# Sprite_Sail.net
KiCad netlist of a schematic drawn in EAGLE
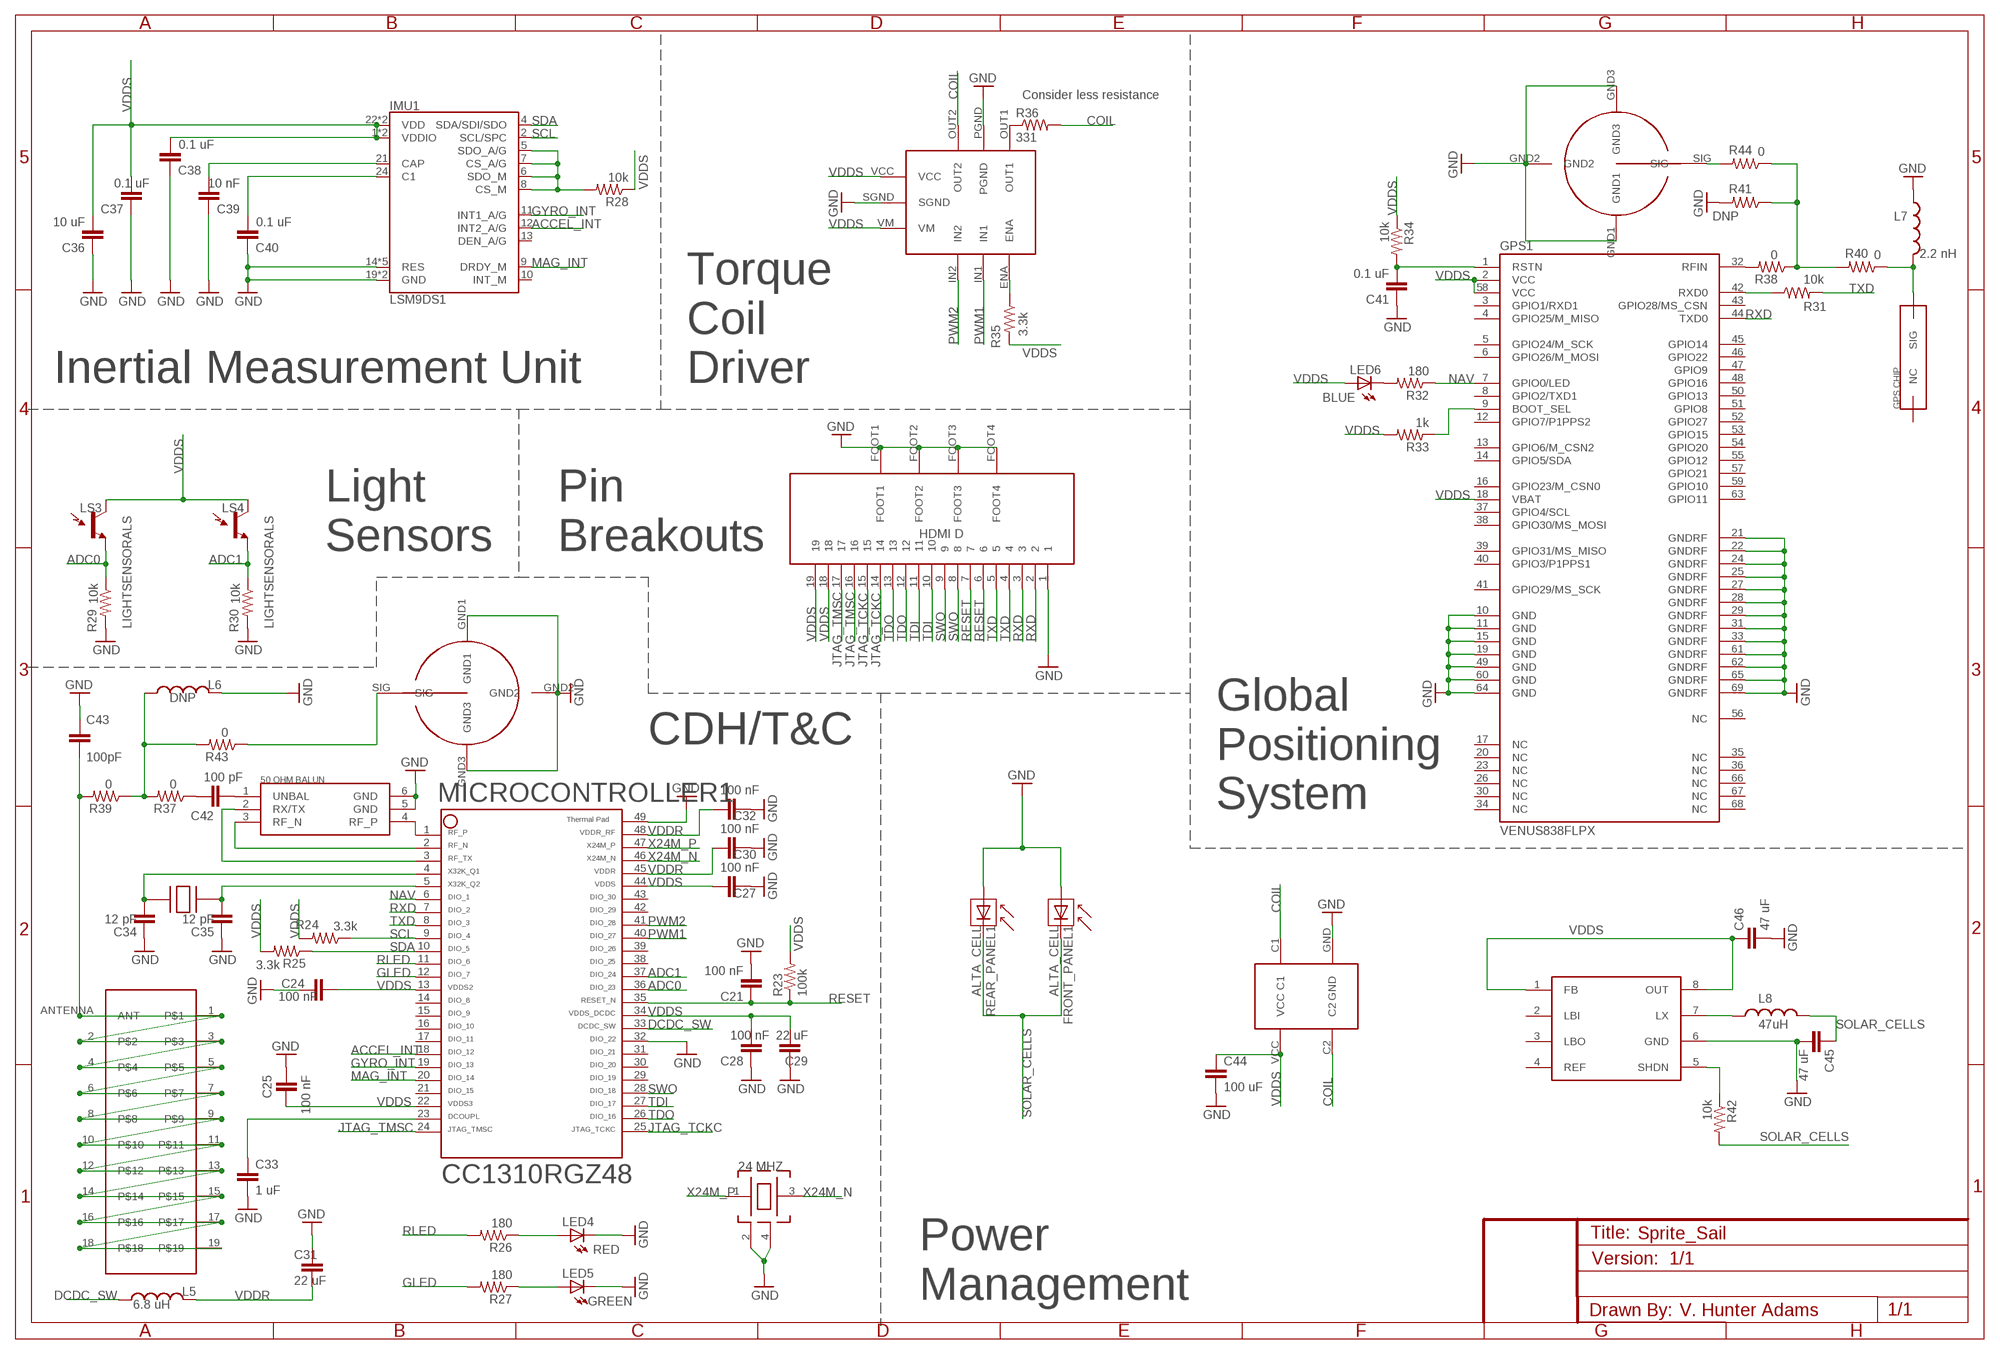
[diagram p0: schematic, sheet 1]

(export (version "E")
  (design (tool "Eeschema 10.0.6"))
  (components
    (comp (ref "32.1")
      (value "FC-135")
      (footprint "eagle-import:FC-135")
      (libsource (lib "eagle-import") (part "FC-135"))
    )
    (comp (ref "BALUN1")
      (value "JOHANSON_BALUN")
      (footprint "eagle-import:JOHANSON_BALUN")
      (libsource (lib "eagle-import") (part "JOHANSON_BALUN"))
    )
    (comp (ref "C21")
      (value "100 nF")
      (footprint "eagle-import:0402-CAP")
      (libsource (lib "eagle-import") (part "CAP0402-CAP"))
    )
    (comp (ref "C24")
      (value "100 nF")
      (footprint "eagle-import:0402-CAP")
      (libsource (lib "eagle-import") (part "CAP0402-CAP"))
    )
    (comp (ref "C25")
      (value "100 nF")
      (footprint "eagle-import:0402-CAP")
      (libsource (lib "eagle-import") (part "CAP0402-CAP"))
    )
    (comp (ref "C27")
      (value "100 nF")
      (footprint "eagle-import:0402-CAP")
      (libsource (lib "eagle-import") (part "CAP0402-CAP"))
    )
    (comp (ref "C28")
      (value "100 nF")
      (footprint "eagle-import:0402-CAP")
      (libsource (lib "eagle-import") (part "CAP0402-CAP"))
    )
    (comp (ref "C29")
      (value "22 uF")
      (footprint "eagle-import:0402-CAP")
      (libsource (lib "eagle-import") (part "CAP0402-CAP"))
    )
    (comp (ref "C30")
      (value "100 nF")
      (footprint "eagle-import:0402-CAP")
      (libsource (lib "eagle-import") (part "CAP0402-CAP"))
    )
    (comp (ref "C31")
      (value "22 uF")
      (footprint "eagle-import:0402-CAP")
      (libsource (lib "eagle-import") (part "CAP0402-CAP"))
    )
    (comp (ref "C32")
      (value "100 nF")
      (footprint "eagle-import:0402-CAP")
      (libsource (lib "eagle-import") (part "CAP0402-CAP"))
    )
    (comp (ref "C33")
      (value "1 uF")
      (footprint "eagle-import:0402-CAP")
      (libsource (lib "eagle-import") (part "CAP0402-CAP"))
    )
    (comp (ref "C34")
      (value "12 pF")
      (footprint "eagle-import:0402-CAP")
      (libsource (lib "eagle-import") (part "CAP0402-CAP"))
    )
    (comp (ref "C35")
      (value "12 pF")
      (footprint "eagle-import:0402-CAP")
      (libsource (lib "eagle-import") (part "CAP0402-CAP"))
    )
    (comp (ref "C36")
      (value "10 uF")
      (footprint "eagle-import:0402-CAP")
      (libsource (lib "eagle-import") (part "CAP0402-CAP"))
    )
    (comp (ref "C37")
      (value "0.1 uF")
      (footprint "eagle-import:0402-CAP")
      (libsource (lib "eagle-import") (part "CAP0402-CAP"))
    )
    (comp (ref "C38")
      (value "0.1 uF")
      (footprint "eagle-import:0402-CAP")
      (libsource (lib "eagle-import") (part "CAP0402-CAP"))
    )
    (comp (ref "C39")
      (value "10 nF")
      (footprint "eagle-import:0402-CAP")
      (libsource (lib "eagle-import") (part "CAP0402-CAP"))
    )
    (comp (ref "C40")
      (value "0.1 uF")
      (footprint "eagle-import:0402-CAP")
      (libsource (lib "eagle-import") (part "CAP0402-CAP"))
    )
    (comp (ref "C41")
      (value "0.1 uF")
      (footprint "eagle-import:0402-CAP")
      (libsource (lib "eagle-import") (part "CAP0402-CAP"))
    )
    (comp (ref "C42")
      (value "100 pF")
      (footprint "eagle-import:0402-CAP")
      (libsource (lib "eagle-import") (part "CAP0402-CAP"))
    )
    (comp (ref "C43")
      (value "100pF")
      (footprint "eagle-import:0603-CAP")
      (libsource (lib "eagle-import") (part "CAP0603-CAP"))
    )
    (comp (ref "C44")
      (value "100 uF")
      (footprint "eagle-import:0805")
      (libsource (lib "eagle-import") (part "CAP0805"))
    )
    (comp (ref "C45")
      (value "47 uF")
      (footprint "eagle-import:0805")
      (libsource (lib "eagle-import") (part "CAP0805"))
    )
    (comp (ref "C46")
      (value "47 uF")
      (footprint "eagle-import:0805")
      (libsource (lib "eagle-import") (part "CAP0805"))
    )
    (comp (ref "FRONT_PANEL1")
      (value "ALTA_CELL")
      (footprint "eagle-import:ALTA_CELL")
      (libsource (lib "eagle-import") (part "ALTA_CELL"))
    )
    (comp (ref "GPS1")
      (value "VENUS838FLPX")
      (footprint "eagle-import:VENUS838FLPX")
      (libsource (lib "eagle-import") (part "VENUS838FLPX"))
    )
    (comp (ref "IMU1")
      (value "LSM9DS1")
      (footprint "eagle-import:LGA24-8X4")
      (libsource (lib "eagle-import") (part "LSM9DS1"))
    )
    (comp (ref "L5")
      (value "6.8 uH")
      (footprint "eagle-import:0603")
      (libsource (lib "eagle-import") (part "INDUCTOR0603"))
    )
    (comp (ref "L6")
      (value "DNP")
      (footprint "eagle-import:0603")
      (libsource (lib "eagle-import") (part "INDUCTOR0603"))
    )
    (comp (ref "L7")
      (value "2.2 nH")
      (footprint "eagle-import:0603")
      (libsource (lib "eagle-import") (part "INDUCTOR0603"))
    )
    (comp (ref "L8")
      (value "47uH")
      (footprint "eagle-import:0603")
      (libsource (lib "eagle-import") (part "INDUCTOR0603"))
    )
    (comp (ref "LED4")
      (value "RED")
      (footprint "eagle-import:LED-0603")
      (libsource (lib "eagle-import") (part "LED0603"))
    )
    (comp (ref "LED5")
      (value "GREEN")
      (footprint "eagle-import:LED-0603")
      (libsource (lib "eagle-import") (part "LED0603"))
    )
    (comp (ref "LED6")
      (value "BLUE")
      (footprint "eagle-import:LED-0603")
      (libsource (lib "eagle-import") (part "LED0603"))
    )
    (comp (ref "LS3")
      (value "LIGHTSENSORALS")
      (footprint "eagle-import:ALS-PT19")
      (libsource (lib "eagle-import") (part "LIGHTSENSORALS"))
    )
    (comp (ref "LS4")
      (value "LIGHTSENSORALS")
      (footprint "eagle-import:ALS-PT19")
      (libsource (lib "eagle-import") (part "LIGHTSENSORALS"))
    )
    (comp (ref "MICROCONTROLLER1")
      (value "CC1310")
      (footprint "eagle-import:CC1310")
      (libsource (lib "eagle-import") (part "CC1310"))
    )
    (comp (ref "R23")
      (value "100k")
      (footprint "eagle-import:0402-RES")
      (libsource (lib "eagle-import") (part "RESISTOR0402-RES"))
    )
    (comp (ref "R24")
      (value "3.3k")
      (footprint "eagle-import:0402-RES")
      (libsource (lib "eagle-import") (part "RESISTOR0402-RES"))
    )
    (comp (ref "R25")
      (value "3.3k")
      (footprint "eagle-import:0402-RES")
      (libsource (lib "eagle-import") (part "RESISTOR0402-RES"))
    )
    (comp (ref "R26")
      (value "180")
      (footprint "eagle-import:0402-RES")
      (libsource (lib "eagle-import") (part "RESISTOR0402-RES"))
    )
    (comp (ref "R27")
      (value "180")
      (footprint "eagle-import:0402-RES")
      (libsource (lib "eagle-import") (part "RESISTOR0402-RES"))
    )
    (comp (ref "R28")
      (value "10k")
      (footprint "eagle-import:0402-RES")
      (libsource (lib "eagle-import") (part "RESISTOR0402-RES"))
    )
    (comp (ref "R29")
      (value "10k")
      (footprint "eagle-import:0402-RES")
      (libsource (lib "eagle-import") (part "RESISTOR0402-RES"))
    )
    (comp (ref "R30")
      (value "10k")
      (footprint "eagle-import:0402-RES")
      (libsource (lib "eagle-import") (part "RESISTOR0402-RES"))
    )
    (comp (ref "R31")
      (value "10k")
      (footprint "eagle-import:0402-RES")
      (libsource (lib "eagle-import") (part "RESISTOR0402-RES"))
    )
    (comp (ref "R32")
      (value "180")
      (footprint "eagle-import:0402-RES")
      (libsource (lib "eagle-import") (part "RESISTOR0402-RES"))
    )
    (comp (ref "R33")
      (value "1k")
      (footprint "eagle-import:0402-RES")
      (libsource (lib "eagle-import") (part "RESISTOR0402-RES"))
    )
    (comp (ref "R34")
      (value "10k")
      (footprint "eagle-import:0402-RES")
      (libsource (lib "eagle-import") (part "RESISTOR0402-RES"))
    )
    (comp (ref "R35")
      (value "3.3k")
      (footprint "eagle-import:0402-RES")
      (libsource (lib "eagle-import") (part "RESISTOR0402-RES"))
    )
    (comp (ref "R36")
      (value "331")
      (footprint "eagle-import:0402-RES")
      (libsource (lib "eagle-import") (part "RESISTOR0402-RES"))
    )
    (comp (ref "R37")
      (value "0")
      (footprint "eagle-import:0603-RES")
      (libsource (lib "eagle-import") (part "RESISTOR0603-RES"))
    )
    (comp (ref "R38")
      (value "0")
      (footprint "eagle-import:0603-RES")
      (libsource (lib "eagle-import") (part "RESISTOR0603-RES"))
    )
    (comp (ref "R39")
      (value "0")
      (footprint "eagle-import:0603-RES")
      (libsource (lib "eagle-import") (part "RESISTOR0603-RES"))
    )
    (comp (ref "R40")
      (value "0")
      (footprint "eagle-import:0603-RES")
      (libsource (lib "eagle-import") (part "RESISTOR0603-RES"))
    )
    (comp (ref "R41")
      (value "DNP")
      (footprint "eagle-import:0603-RES")
      (libsource (lib "eagle-import") (part "RESISTOR0603-RES"))
    )
    (comp (ref "R42")
      (value "10k")
      (footprint "eagle-import:0402-RES")
      (libsource (lib "eagle-import") (part "RESISTOR0402-RES"))
    )
    (comp (ref "R43")
      (value "0")
      (footprint "eagle-import:0603-RES")
      (libsource (lib "eagle-import") (part "RESISTOR0603-RES"))
    )
    (comp (ref "R44")
      (value "0")
      (footprint "eagle-import:0603-RES")
      (libsource (lib "eagle-import") (part "RESISTOR0603-RES"))
    )
    (comp (ref "REAR_PANEL1")
      (value "ALTA_CELL")
      (footprint "eagle-import:ALTA_CELL")
      (libsource (lib "eagle-import") (part "ALTA_CELL"))
    )
    (comp (ref "TSX1")
      (value "TSX-3225")
      (footprint "eagle-import:TSX-3225")
      (libsource (lib "eagle-import") (part "TSX-3225"))
    )
    (comp (ref "U$1")
      (value "LV8417CS")
      (footprint "eagle-import:LV8417CS")
      (libsource (lib "eagle-import") (part "LV8417CS"))
    )
    (comp (ref "U$10")
      (value "JOHANSON_GPS_CHIP")
      (footprint "eagle-import:JOHANSON_GPS_CHIP")
      (libsource (lib "eagle-import") (part "JOHANSON_GPS_CHIP"))
    )
    (comp (ref "U$11")
      (value "PANASONIC_RECTIFIER")
      (footprint "eagle-import:PANASONIC_RECTIFIER")
      (libsource (lib "eagle-import") (part "PANASONIC_RECTIFIER"))
    )
    (comp (ref "U$12")
      (value "PCB_ANTENNA")
      (footprint "eagle-import:PCB_ANTENNA")
      (libsource (lib "eagle-import") (part "PCB_ANTENNA"))
    )
    (comp (ref "U$13")
      (value "MM5329-2700")
      (footprint "eagle-import:MM5829-2700")
      (libsource (lib "eagle-import") (part "MM5329-2700"))
    )
    (comp (ref "U$14")
      (value "MM5329-2700")
      (footprint "eagle-import:MM5829-2700")
      (libsource (lib "eagle-import") (part "MM5329-2700"))
    )
    (comp (ref "U$15")
      (value "L6920")
      (footprint "eagle-import:L6920")
      (libsource (lib "eagle-import") (part "L6920"))
    )
    (comp (ref "U$16")
      (value "HDMID")
      (footprint "eagle-import:HDMID")
      (libsource (lib "eagle-import") (part "HDMID"))
    )
  )
  (nets
    (net (code "1") (name "/ACCEL_INT") (class "Default")
      (node (ref "IMU1") (pin "12") (pinfunction "INT2_A/G_12") (pintype "bidirectional"))
      (node (ref "MICROCONTROLLER1") (pin "18") (pinfunction "18_18") (pintype "bidirectional"))
    )
    (net (code "2") (name "/ADC0") (class "Default")
      (node (ref "LS3") (pin "E") (pinfunction "E1_E") (pintype "passive"))
      (node (ref "MICROCONTROLLER1") (pin "36") (pinfunction "36_36") (pintype "bidirectional"))
      (node (ref "R29") (pin "1") (pinfunction "1_1") (pintype "passive"))
    )
    (net (code "3") (name "/ADC1") (class "Default")
      (node (ref "LS4") (pin "E") (pinfunction "E1_E") (pintype "passive"))
      (node (ref "MICROCONTROLLER1") (pin "37") (pinfunction "37_37") (pintype "bidirectional"))
      (node (ref "R30") (pin "1") (pinfunction "1_1") (pintype "passive"))
    )
    (net (code "4") (name "/COIL") (class "Default")
      (node (ref "R36") (pin "2") (pinfunction "2_2") (pintype "passive"))
      (node (ref "U$1") (pin "OUT2") (pinfunction "OUT2_OUT2") (pintype "bidirectional"))
      (node (ref "U$11") (pin "C1") (pinfunction "C1_C1") (pintype "bidirectional"))
      (node (ref "U$11") (pin "C2") (pinfunction "C2_C2") (pintype "bidirectional"))
    )
    (net (code "5") (name "/DCDC_SW") (class "Default")
      (node (ref "L5") (pin "1") (pinfunction "1_1") (pintype "passive"))
      (node (ref "MICROCONTROLLER1") (pin "33") (pinfunction "33_33") (pintype "power_in"))
    )
    (net (code "6") (name "/GLED") (class "Default")
      (node (ref "MICROCONTROLLER1") (pin "12") (pinfunction "12_12") (pintype "bidirectional"))
      (node (ref "R27") (pin "2") (pinfunction "2_2") (pintype "passive"))
    )
    (net (code "7") (name "/GYRO_INT") (class "Default")
      (node (ref "IMU1") (pin "11") (pinfunction "INT1_A/G_11") (pintype "bidirectional"))
      (node (ref "MICROCONTROLLER1") (pin "19") (pinfunction "19_19") (pintype "bidirectional"))
    )
    (net (code "8") (name "/JTAG_TCKC") (class "Default")
      (node (ref "MICROCONTROLLER1") (pin "25") (pinfunction "25_25") (pintype "input"))
      (node (ref "U$16") (pin "14") (pinfunction "14_14") (pintype "bidirectional"))
      (node (ref "U$16") (pin "15") (pinfunction "15_15") (pintype "bidirectional"))
    )
    (net (code "9") (name "/JTAG_TMSC") (class "Default")
      (node (ref "MICROCONTROLLER1") (pin "24") (pinfunction "24_24") (pintype "bidirectional"))
      (node (ref "U$16") (pin "16") (pinfunction "16_16") (pintype "bidirectional"))
      (node (ref "U$16") (pin "17") (pinfunction "17_17") (pintype "bidirectional"))
    )
    (net (code "10") (name "/MAG_INT") (class "Default")
      (node (ref "IMU1") (pin "9") (pinfunction "DRDY_M_9") (pintype "bidirectional"))
      (node (ref "MICROCONTROLLER1") (pin "20") (pinfunction "20_20") (pintype "bidirectional"))
    )
    (net (code "11") (name "/NAV") (class "Default")
      (node (ref "GPS1") (pin "7") (pinfunction "GPIO0/LED_7") (pintype "bidirectional"))
      (node (ref "MICROCONTROLLER1") (pin "6") (pinfunction "6_6") (pintype "bidirectional"))
      (node (ref "R32") (pin "1") (pinfunction "1_1") (pintype "passive"))
    )
    (net (code "12") (name "/PWM1") (class "Default")
      (node (ref "MICROCONTROLLER1") (pin "40") (pinfunction "40_40") (pintype "bidirectional"))
      (node (ref "U$1") (pin "IN1") (pinfunction "IN1_IN1") (pintype "bidirectional"))
    )
    (net (code "13") (name "/PWM2") (class "Default")
      (node (ref "MICROCONTROLLER1") (pin "41") (pinfunction "41_41") (pintype "bidirectional"))
      (node (ref "U$1") (pin "IN2") (pinfunction "IN2_IN2") (pintype "bidirectional"))
    )
    (net (code "14") (name "/RESET") (class "Default")
      (node (ref "C21") (pin "1") (pinfunction "1_1") (pintype "passive"))
      (node (ref "MICROCONTROLLER1") (pin "35") (pinfunction "35_35") (pintype "input"))
      (node (ref "R23") (pin "1") (pinfunction "1_1") (pintype "passive"))
      (node (ref "U$16") (pin "6") (pinfunction "6_6") (pintype "bidirectional"))
      (node (ref "U$16") (pin "7") (pinfunction "7_7") (pintype "bidirectional"))
    )
    (net (code "15") (name "/RLED") (class "Default")
      (node (ref "MICROCONTROLLER1") (pin "11") (pinfunction "11_11") (pintype "bidirectional"))
      (node (ref "R26") (pin "2") (pinfunction "2_2") (pintype "passive"))
    )
    (net (code "16") (name "/RXD") (class "Default")
      (node (ref "GPS1") (pin "44") (pinfunction "TXD0_44") (pintype "bidirectional"))
      (node (ref "MICROCONTROLLER1") (pin "7") (pinfunction "7_7") (pintype "bidirectional"))
      (node (ref "U$16") (pin "2") (pinfunction "2_2") (pintype "bidirectional"))
      (node (ref "U$16") (pin "3") (pinfunction "3_3") (pintype "bidirectional"))
    )
    (net (code "17") (name "/SCL") (class "Default")
      (node (ref "IMU1") (pin "2") (pinfunction "SCL/SPC_2") (pintype "bidirectional"))
      (node (ref "MICROCONTROLLER1") (pin "9") (pinfunction "9_9") (pintype "bidirectional"))
      (node (ref "R24") (pin "1") (pinfunction "1_1") (pintype "passive"))
    )
    (net (code "18") (name "/SDA") (class "Default")
      (node (ref "IMU1") (pin "4") (pinfunction "SDA/SDI/SDO_4") (pintype "bidirectional"))
      (node (ref "MICROCONTROLLER1") (pin "10") (pinfunction "10_10") (pintype "bidirectional"))
      (node (ref "R25") (pin "1") (pinfunction "1_1") (pintype "passive"))
    )
    (net (code "19") (name "/SOLAR_CELLS") (class "Default")
      (node (ref "C45") (pin "1") (pinfunction "1_1") (pintype "passive"))
      (node (ref "FRONT_PANEL1") (pin "+") (pinfunction "+_+") (pintype "passive"))
      (node (ref "L8") (pin "2") (pinfunction "2_2") (pintype "passive"))
      (node (ref "R42") (pin "2") (pinfunction "2_2") (pintype "passive"))
      (node (ref "REAR_PANEL1") (pin "+") (pinfunction "+_+") (pintype "passive"))
    )
    (net (code "20") (name "/SWO") (class "Default")
      (node (ref "MICROCONTROLLER1") (pin "28") (pinfunction "28_28") (pintype "bidirectional"))
      (node (ref "U$16") (pin "8") (pinfunction "8_8") (pintype "bidirectional"))
      (node (ref "U$16") (pin "9") (pinfunction "9_9") (pintype "bidirectional"))
    )
    (net (code "21") (name "/TDI") (class "Default")
      (node (ref "MICROCONTROLLER1") (pin "27") (pinfunction "27_27") (pintype "bidirectional"))
      (node (ref "U$16") (pin "10") (pinfunction "10_10") (pintype "bidirectional"))
      (node (ref "U$16") (pin "11") (pinfunction "11_11") (pintype "bidirectional"))
    )
    (net (code "22") (name "/TDO") (class "Default")
      (node (ref "MICROCONTROLLER1") (pin "26") (pinfunction "26_26") (pintype "bidirectional"))
      (node (ref "U$16") (pin "12") (pinfunction "12_12") (pintype "bidirectional"))
      (node (ref "U$16") (pin "13") (pinfunction "13_13") (pintype "bidirectional"))
    )
    (net (code "23") (name "/TXD") (class "Default")
      (node (ref "MICROCONTROLLER1") (pin "8") (pinfunction "8_8") (pintype "bidirectional"))
      (node (ref "R31") (pin "2") (pinfunction "2_2") (pintype "passive"))
      (node (ref "U$16") (pin "4") (pinfunction "4_4") (pintype "bidirectional"))
      (node (ref "U$16") (pin "5") (pinfunction "5_5") (pintype "bidirectional"))
    )
    (net (code "24") (name "/VDDR") (class "Default")
      (node (ref "C30") (pin "1") (pinfunction "1_1") (pintype "passive"))
      (node (ref "C31") (pin "1") (pinfunction "1_1") (pintype "passive"))
      (node (ref "C32") (pin "1") (pinfunction "1_1") (pintype "passive"))
      (node (ref "L5") (pin "2") (pinfunction "2_2") (pintype "passive"))
      (node (ref "MICROCONTROLLER1") (pin "45") (pinfunction "45_45") (pintype "power_in"))
      (node (ref "MICROCONTROLLER1") (pin "48") (pinfunction "48_48") (pintype "power_in"))
    )
    (net (code "25") (name "/VDDS") (class "Default")
      (node (ref "C24") (pin "1") (pinfunction "1_1") (pintype "passive"))
      (node (ref "C25") (pin "1") (pinfunction "1_1") (pintype "passive"))
      (node (ref "C27") (pin "1") (pinfunction "1_1") (pintype "passive"))
      (node (ref "C28") (pin "1") (pinfunction "1_1") (pintype "passive"))
      (node (ref "C29") (pin "1") (pinfunction "1_1") (pintype "passive"))
      (node (ref "C36") (pin "1") (pinfunction "1_1") (pintype "passive"))
      (node (ref "C37") (pin "1") (pinfunction "1_1") (pintype "passive"))
      (node (ref "C38") (pin "1") (pinfunction "1_1") (pintype "passive"))
      (node (ref "C44") (pin "1") (pinfunction "1_1") (pintype "passive"))
      (node (ref "C46") (pin "1") (pinfunction "1_1") (pintype "passive"))
      (node (ref "GPS1") (pin "18") (pinfunction "VBAT_18") (pintype "bidirectional"))
      (node (ref "GPS1") (pin "2") (pinfunction "VCC_2") (pintype "bidirectional"))
      (node (ref "GPS1") (pin "58") (pinfunction "VCC_58") (pintype "bidirectional"))
      (node (ref "IMU1") (pin "1") (pinfunction "VDDIO_1") (pintype "bidirectional"))
      (node (ref "IMU1") (pin "22") (pinfunction "VDD_22") (pintype "bidirectional"))
      (node (ref "IMU1") (pin "23") (pinfunction "VDD_23") (pintype "bidirectional"))
      (node (ref "IMU1") (pin "3") (pinfunction "VDDIO_3") (pintype "bidirectional"))
      (node (ref "LED6") (pin "A") (pinfunction "A_A") (pintype "passive"))
      (node (ref "LS3") (pin "C") (pinfunction "C1_C") (pintype "passive"))
      (node (ref "LS4") (pin "C") (pinfunction "C1_C") (pintype "passive"))
      (node (ref "MICROCONTROLLER1") (pin "13") (pinfunction "13_13") (pintype "bidirectional"))
      (node (ref "MICROCONTROLLER1") (pin "22") (pinfunction "22_22") (pintype "power_in"))
      (node (ref "MICROCONTROLLER1") (pin "34") (pinfunction "34_34") (pintype "power_in"))
      (node (ref "MICROCONTROLLER1") (pin "44") (pinfunction "44_44") (pintype "power_in"))
      (node (ref "R23") (pin "2") (pinfunction "2_2") (pintype "passive"))
      (node (ref "R24") (pin "2") (pinfunction "2_2") (pintype "passive"))
      (node (ref "R25") (pin "2") (pinfunction "2_2") (pintype "passive"))
      (node (ref "R28") (pin "1") (pinfunction "1_1") (pintype "passive"))
      (node (ref "R33") (pin "2") (pinfunction "2_2") (pintype "passive"))
      (node (ref "R34") (pin "1") (pinfunction "1_1") (pintype "passive"))
      (node (ref "R35") (pin "2") (pinfunction "2_2") (pintype "passive"))
      (node (ref "U$1") (pin "VCC") (pinfunction "VCC_VCC") (pintype "bidirectional"))
      (node (ref "U$1") (pin "VM") (pinfunction "VM_VM") (pintype "bidirectional"))
      (node (ref "U$11") (pin "VCC") (pinfunction "VCC_VCC") (pintype "bidirectional"))
      (node (ref "U$15") (pin "1") (pinfunction "FB_1") (pintype "bidirectional"))
      (node (ref "U$15") (pin "8") (pinfunction "OUT_8") (pintype "bidirectional"))
      (node (ref "U$16") (pin "18") (pinfunction "18_18") (pintype "bidirectional"))
      (node (ref "U$16") (pin "19") (pinfunction "19_19") (pintype "bidirectional"))
    )
    (net (code "26") (name "/X24M_N") (class "Default")
      (node (ref "MICROCONTROLLER1") (pin "46") (pinfunction "46_46") (pintype "bidirectional"))
      (node (ref "TSX1") (pin "3") (pinfunction "3_3") (pintype "bidirectional"))
    )
    (net (code "27") (name "/X24M_P") (class "Default")
      (node (ref "MICROCONTROLLER1") (pin "47") (pinfunction "47_47") (pintype "input"))
      (node (ref "TSX1") (pin "1") (pinfunction "1_1") (pintype "bidirectional"))
    )
    (net (code "28") (name "GND") (class "Default")
      (node (ref "BALUN1") (pin "5") (pinfunction "GND_5") (pintype "bidirectional"))
      (node (ref "BALUN1") (pin "6") (pinfunction "GND_6") (pintype "bidirectional"))
      (node (ref "C21") (pin "2") (pinfunction "2_2") (pintype "passive"))
      (node (ref "C24") (pin "2") (pinfunction "2_2") (pintype "passive"))
      (node (ref "C25") (pin "2") (pinfunction "2_2") (pintype "passive"))
      (node (ref "C27") (pin "2") (pinfunction "2_2") (pintype "passive"))
      (node (ref "C28") (pin "2") (pinfunction "2_2") (pintype "passive"))
      (node (ref "C29") (pin "2") (pinfunction "2_2") (pintype "passive"))
      (node (ref "C30") (pin "2") (pinfunction "2_2") (pintype "passive"))
      (node (ref "C31") (pin "2") (pinfunction "2_2") (pintype "passive"))
      (node (ref "C32") (pin "2") (pinfunction "2_2") (pintype "passive"))
      (node (ref "C33") (pin "2") (pinfunction "2_2") (pintype "passive"))
      (node (ref "C34") (pin "2") (pinfunction "2_2") (pintype "passive"))
      (node (ref "C35") (pin "2") (pinfunction "2_2") (pintype "passive"))
      (node (ref "C36") (pin "2") (pinfunction "2_2") (pintype "passive"))
      (node (ref "C37") (pin "2") (pinfunction "2_2") (pintype "passive"))
      (node (ref "C38") (pin "2") (pinfunction "2_2") (pintype "passive"))
      (node (ref "C39") (pin "2") (pinfunction "2_2") (pintype "passive"))
      (node (ref "C40") (pin "2") (pinfunction "2_2") (pintype "passive"))
      (node (ref "C41") (pin "2") (pinfunction "2_2") (pintype "passive"))
      (node (ref "C43") (pin "1") (pinfunction "1_1") (pintype "passive"))
      (node (ref "C44") (pin "2") (pinfunction "2_2") (pintype "passive"))
      (node (ref "C45") (pin "2") (pinfunction "2_2") (pintype "passive"))
      (node (ref "C46") (pin "2") (pinfunction "2_2") (pintype "passive"))
      (node (ref "FRONT_PANEL1") (pin "-") (pinfunction "-_-") (pintype "passive"))
      (node (ref "GPS1") (pin "10") (pinfunction "GND_10") (pintype "bidirectional"))
      (node (ref "GPS1") (pin "11") (pinfunction "GND_11") (pintype "bidirectional"))
      (node (ref "GPS1") (pin "15") (pinfunction "GND_15") (pintype "bidirectional"))
      (node (ref "GPS1") (pin "19") (pinfunction "GND_19") (pintype "bidirectional"))
      (node (ref "GPS1") (pin "21") (pinfunction "GNDRF_21") (pintype "bidirectional"))
      (node (ref "GPS1") (pin "22") (pinfunction "GNDRF_22") (pintype "bidirectional"))
      (node (ref "GPS1") (pin "24") (pinfunction "GNDRF_24") (pintype "bidirectional"))
      (node (ref "GPS1") (pin "25") (pinfunction "GNDRF_25") (pintype "bidirectional"))
      (node (ref "GPS1") (pin "27") (pinfunction "GNDRF_27") (pintype "bidirectional"))
      (node (ref "GPS1") (pin "28") (pinfunction "GNDRF_28") (pintype "bidirectional"))
      (node (ref "GPS1") (pin "29") (pinfunction "GNDRF_29") (pintype "bidirectional"))
      (node (ref "GPS1") (pin "31") (pinfunction "GNDRF_31") (pintype "bidirectional"))
      (node (ref "GPS1") (pin "33") (pinfunction "GNDRF_33") (pintype "bidirectional"))
      (node (ref "GPS1") (pin "49") (pinfunction "GND_49") (pintype "bidirectional"))
      (node (ref "GPS1") (pin "60") (pinfunction "GND_60") (pintype "bidirectional"))
      (node (ref "GPS1") (pin "61") (pinfunction "GNDRF_61") (pintype "bidirectional"))
      (node (ref "GPS1") (pin "62") (pinfunction "GNDRF_62") (pintype "bidirectional"))
      (node (ref "GPS1") (pin "64") (pinfunction "GND_64") (pintype "bidirectional"))
      (node (ref "GPS1") (pin "65") (pinfunction "GNDRF_65") (pintype "bidirectional"))
      (node (ref "GPS1") (pin "69") (pinfunction "GNDRF_69") (pintype "bidirectional"))
      (node (ref "IMU1") (pin "14") (pinfunction "RES_14") (pintype "bidirectional"))
      (node (ref "IMU1") (pin "15") (pinfunction "RES_15") (pintype "bidirectional"))
      (node (ref "IMU1") (pin "16") (pinfunction "RES_16") (pintype "bidirectional"))
      (node (ref "IMU1") (pin "17") (pinfunction "RES_17") (pintype "bidirectional"))
      (node (ref "IMU1") (pin "18") (pinfunction "RES_18") (pintype "bidirectional"))
      (node (ref "IMU1") (pin "19") (pinfunction "GND_19") (pintype "bidirectional"))
      (node (ref "IMU1") (pin "20") (pinfunction "GND_20") (pintype "bidirectional"))
      (node (ref "L6") (pin "2") (pinfunction "2_2") (pintype "passive"))
      (node (ref "L7") (pin "1") (pinfunction "1_1") (pintype "passive"))
      (node (ref "LED4") (pin "C") (pinfunction "C_C") (pintype "passive"))
      (node (ref "LED5") (pin "C") (pinfunction "C_C") (pintype "passive"))
      (node (ref "MICROCONTROLLER1") (pin "32") (pinfunction "32_32") (pintype "bidirectional"))
      (node (ref "MICROCONTROLLER1") (pin "49") (pinfunction "49_49") (pintype "input"))
      (node (ref "R29") (pin "2") (pinfunction "2_2") (pintype "passive"))
      (node (ref "R30") (pin "2") (pinfunction "2_2") (pintype "passive"))
      (node (ref "R41") (pin "2") (pinfunction "2_2") (pintype "passive"))
      (node (ref "REAR_PANEL1") (pin "-") (pinfunction "-_-") (pintype "passive"))
      (node (ref "TSX1") (pin "2") (pinfunction "2_2") (pintype "bidirectional"))
      (node (ref "TSX1") (pin "4") (pinfunction "4_4") (pintype "bidirectional"))
      (node (ref "U$1") (pin "PGND") (pinfunction "PGND_PGND") (pintype "bidirectional"))
      (node (ref "U$1") (pin "SGND") (pinfunction "SGND_SGND") (pintype "bidirectional"))
      (node (ref "U$11") (pin "GND") (pinfunction "GND_GND") (pintype "bidirectional"))
      (node (ref "U$13") (pin "GND1") (pinfunction "GND1_GND1") (pintype "bidirectional"))
      (node (ref "U$13") (pin "GND2") (pinfunction "GND2_GND2") (pintype "bidirectional"))
      (node (ref "U$13") (pin "GND3") (pinfunction "GND3_GND3") (pintype "bidirectional"))
      (node (ref "U$14") (pin "GND1") (pinfunction "GND1_GND1") (pintype "bidirectional"))
      (node (ref "U$14") (pin "GND2") (pinfunction "GND2_GND2") (pintype "bidirectional"))
      (node (ref "U$14") (pin "GND3") (pinfunction "GND3_GND3") (pintype "bidirectional"))
      (node (ref "U$15") (pin "6") (pinfunction "GND_6") (pintype "bidirectional"))
      (node (ref "U$16") (pin "1") (pinfunction "1_1") (pintype "bidirectional"))
      (node (ref "U$16") (pin "FOOT1") (pinfunction "FOOT1_FOOT1") (pintype "bidirectional"))
      (node (ref "U$16") (pin "FOOT2") (pinfunction "FOOT2_FOOT2") (pintype "bidirectional"))
      (node (ref "U$16") (pin "FOOT3") (pinfunction "FOOT3_FOOT3") (pintype "bidirectional"))
      (node (ref "U$16") (pin "FOOT4") (pinfunction "FOOT4_FOOT4") (pintype "bidirectional"))
    )
    (net (code "29") (name "Net-(32.1-PadP1)") (class "Default")
      (node (ref "32.1") (pin "P1") (pinfunction "P1_P1") (pintype "bidirectional"))
      (node (ref "C35") (pin "1") (pinfunction "1_1") (pintype "passive"))
      (node (ref "MICROCONTROLLER1") (pin "5") (pinfunction "5_5") (pintype "bidirectional"))
    )
    (net (code "30") (name "Net-(32.1-PadP2)") (class "Default")
      (node (ref "32.1") (pin "P2") (pinfunction "P2_P2") (pintype "bidirectional"))
      (node (ref "C34") (pin "1") (pinfunction "1_1") (pintype "passive"))
      (node (ref "MICROCONTROLLER1") (pin "4") (pinfunction "4_4") (pintype "bidirectional"))
    )
    (net (code "31") (name "Net-(BALUN1-RF_N)") (class "Default")
      (node (ref "BALUN1") (pin "3") (pinfunction "RF_N_3") (pintype "bidirectional"))
      (node (ref "MICROCONTROLLER1") (pin "2") (pinfunction "2_2") (pintype "bidirectional"))
    )
    (net (code "32") (name "Net-(BALUN1-RF_P)") (class "Default")
      (node (ref "BALUN1") (pin "4") (pinfunction "RF_P_4") (pintype "bidirectional"))
      (node (ref "MICROCONTROLLER1") (pin "1") (pinfunction "1_1") (pintype "bidirectional"))
    )
    (net (code "33") (name "Net-(BALUN1-RX{slash}TX)") (class "Default")
      (node (ref "BALUN1") (pin "2") (pinfunction "RX/TX_2") (pintype "bidirectional"))
      (node (ref "MICROCONTROLLER1") (pin "3") (pinfunction "3_3") (pintype "bidirectional"))
    )
    (net (code "34") (name "Net-(BALUN1-UNBAL)") (class "Default")
      (node (ref "BALUN1") (pin "1") (pinfunction "UNBAL_1") (pintype "bidirectional"))
      (node (ref "C42") (pin "2") (pinfunction "2_2") (pintype "passive"))
    )
    (net (code "35") (name "Net-(C33-Pad1)") (class "Default")
      (node (ref "C33") (pin "1") (pinfunction "1_1") (pintype "passive"))
      (node (ref "MICROCONTROLLER1") (pin "23") (pinfunction "23_23") (pintype "bidirectional"))
    )
    (net (code "36") (name "Net-(C42-Pad1)") (class "Default")
      (node (ref "C42") (pin "1") (pinfunction "1_1") (pintype "passive"))
      (node (ref "R37") (pin "1") (pinfunction "1_1") (pintype "passive"))
    )
    (net (code "37") (name "Net-(GPS1-BOOT_SEL)") (class "Default")
      (node (ref "GPS1") (pin "9") (pinfunction "BOOT_SEL_9") (pintype "bidirectional"))
      (node (ref "R33") (pin "1") (pinfunction "1_1") (pintype "passive"))
    )
    (net (code "38") (name "Net-(GPS1-RFIN)") (class "Default")
      (node (ref "GPS1") (pin "32") (pinfunction "RFIN_32") (pintype "bidirectional"))
      (node (ref "R38") (pin "2") (pinfunction "2_2") (pintype "passive"))
    )
    (net (code "39") (name "Net-(GPS1-RSTN)") (class "Default")
      (node (ref "C41") (pin "1") (pinfunction "1_1") (pintype "passive"))
      (node (ref "GPS1") (pin "1") (pinfunction "RSTN_1") (pintype "bidirectional"))
      (node (ref "R34") (pin "2") (pinfunction "2_2") (pintype "passive"))
    )
    (net (code "40") (name "Net-(GPS1-RXD0)") (class "Default")
      (node (ref "GPS1") (pin "42") (pinfunction "RXD0_42") (pintype "bidirectional"))
      (node (ref "R31") (pin "1") (pinfunction "1_1") (pintype "passive"))
    )
    (net (code "41") (name "Net-(IMU1-C1)") (class "Default")
      (node (ref "C40") (pin "1") (pinfunction "1_1") (pintype "passive"))
      (node (ref "IMU1") (pin "24") (pinfunction "C1_24") (pintype "bidirectional"))
    )
    (net (code "42") (name "Net-(IMU1-CAP)") (class "Default")
      (node (ref "C39") (pin "1") (pinfunction "1_1") (pintype "passive"))
      (node (ref "IMU1") (pin "21") (pinfunction "CAP_21") (pintype "bidirectional"))
    )
    (net (code "43") (name "Net-(IMU1-CS_A{slash}G)") (class "Default")
      (node (ref "IMU1") (pin "5") (pinfunction "SDO_A/G_5") (pintype "bidirectional"))
      (node (ref "IMU1") (pin "6") (pinfunction "SDO_M_6") (pintype "bidirectional"))
      (node (ref "IMU1") (pin "7") (pinfunction "CS_A/G_7") (pintype "bidirectional"))
      (node (ref "IMU1") (pin "8") (pinfunction "CS_M_8") (pintype "bidirectional"))
      (node (ref "R28") (pin "2") (pinfunction "2_2") (pintype "passive"))
    )
    (net (code "44") (name "Net-(L6-Pad1)") (class "Default")
      (node (ref "L6") (pin "1") (pinfunction "1_1") (pintype "passive"))
      (node (ref "R37") (pin "2") (pinfunction "2_2") (pintype "passive"))
      (node (ref "R39") (pin "1") (pinfunction "1_1") (pintype "passive"))
      (node (ref "R43") (pin "2") (pinfunction "2_2") (pintype "passive"))
    )
    (net (code "45") (name "Net-(L7-Pad2)") (class "Default")
      (node (ref "L7") (pin "2") (pinfunction "2_2") (pintype "passive"))
      (node (ref "R40") (pin "1") (pinfunction "1_1") (pintype "passive"))
      (node (ref "U$10") (pin "SIG") (pinfunction "SIG_SIG") (pintype "bidirectional"))
    )
    (net (code "46") (name "Net-(LED4-PadA)") (class "Default")
      (node (ref "LED4") (pin "A") (pinfunction "A_A") (pintype "passive"))
      (node (ref "R26") (pin "1") (pinfunction "1_1") (pintype "passive"))
    )
    (net (code "47") (name "Net-(LED5-PadA)") (class "Default")
      (node (ref "LED5") (pin "A") (pinfunction "A_A") (pintype "passive"))
      (node (ref "R27") (pin "1") (pinfunction "1_1") (pintype "passive"))
    )
    (net (code "48") (name "Net-(LED6-PadC)") (class "Default")
      (node (ref "LED6") (pin "C") (pinfunction "C_C") (pintype "passive"))
      (node (ref "R32") (pin "2") (pinfunction "2_2") (pintype "passive"))
    )
    (net (code "49") (name "Net-(R35-Pad1)") (class "Default")
      (node (ref "R35") (pin "1") (pinfunction "1_1") (pintype "passive"))
      (node (ref "U$1") (pin "ENA") (pinfunction "ENA_ENA") (pintype "bidirectional"))
    )
    (net (code "50") (name "Net-(R36-Pad1)") (class "Default")
      (node (ref "R36") (pin "1") (pinfunction "1_1") (pintype "passive"))
      (node (ref "U$1") (pin "OUT1") (pinfunction "OUT1_OUT1") (pintype "bidirectional"))
    )
    (net (code "51") (name "Net-(R38-Pad1)") (class "Default")
      (node (ref "R38") (pin "1") (pinfunction "1_1") (pintype "passive"))
      (node (ref "R40") (pin "2") (pinfunction "2_2") (pintype "passive"))
      (node (ref "R41") (pin "1") (pinfunction "1_1") (pintype "passive"))
      (node (ref "R44") (pin "1") (pinfunction "1_1") (pintype "passive"))
    )
    (net (code "52") (name "Net-(R43-Pad1)") (class "Default")
      (node (ref "R43") (pin "1") (pinfunction "1_1") (pintype "passive"))
      (node (ref "U$13") (pin "SIG") (pinfunction "SIG_SIG") (pintype "bidirectional"))
    )
    (net (code "53") (name "Net-(R44-Pad2)") (class "Default")
      (node (ref "R44") (pin "2") (pinfunction "2_2") (pintype "passive"))
      (node (ref "U$14") (pin "SIG") (pinfunction "SIG_SIG") (pintype "bidirectional"))
    )
    (net (code "54") (name "Net-(U$12-ANT)") (class "Default")
      (node (ref "C43") (pin "2") (pinfunction "2_2") (pintype "passive"))
      (node (ref "R39") (pin "2") (pinfunction "2_2") (pintype "passive"))
      (node (ref "U$12") (pin "1") (pinfunction "P$1_1") (pintype "bidirectional"))
      (node (ref "U$12") (pin "10") (pinfunction "P$10_10") (pintype "bidirectional"))
      (node (ref "U$12") (pin "11") (pinfunction "P$11_11") (pintype "bidirectional"))
      (node (ref "U$12") (pin "12") (pinfunction "P$12_12") (pintype "bidirectional"))
      (node (ref "U$12") (pin "13") (pinfunction "P$13_13") (pintype "bidirectional"))
      (node (ref "U$12") (pin "14") (pinfunction "P$14_14") (pintype "bidirectional"))
      (node (ref "U$12") (pin "15") (pinfunction "P$15_15") (pintype "bidirectional"))
      (node (ref "U$12") (pin "16") (pinfunction "P$16_16") (pintype "bidirectional"))
      (node (ref "U$12") (pin "17") (pinfunction "P$17_17") (pintype "bidirectional"))
      (node (ref "U$12") (pin "18") (pinfunction "P$18_18") (pintype "bidirectional"))
      (node (ref "U$12") (pin "19") (pinfunction "P$19_19") (pintype "bidirectional"))
      (node (ref "U$12") (pin "2") (pinfunction "P$2_2") (pintype "bidirectional"))
      (node (ref "U$12") (pin "3") (pinfunction "P$3_3") (pintype "bidirectional"))
      (node (ref "U$12") (pin "4") (pinfunction "P$4_4") (pintype "bidirectional"))
      (node (ref "U$12") (pin "5") (pinfunction "P$5_5") (pintype "bidirectional"))
      (node (ref "U$12") (pin "6") (pinfunction "P$6_6") (pintype "bidirectional"))
      (node (ref "U$12") (pin "7") (pinfunction "P$7_7") (pintype "bidirectional"))
      (node (ref "U$12") (pin "8") (pinfunction "P$8_8") (pintype "bidirectional"))
      (node (ref "U$12") (pin "9") (pinfunction "P$9_9") (pintype "bidirectional"))
      (node (ref "U$12") (pin "ANTENNA") (pinfunction "ANT_ANTENNA") (pintype "bidirectional"))
    )
    (net (code "55") (name "Net-(U$15-LX)") (class "Default")
      (node (ref "L8") (pin "1") (pinfunction "1_1") (pintype "passive"))
      (node (ref "U$15") (pin "7") (pinfunction "LX_7") (pintype "bidirectional"))
    )
    (net (code "56") (name "Net-(U$15-SHDN)") (class "Default")
      (node (ref "R42") (pin "1") (pinfunction "1_1") (pintype "passive"))
      (node (ref "U$15") (pin "5") (pinfunction "SHDN_5") (pintype "bidirectional"))
    )
    (net (code "57") (name "unconnected-(GPS1-GPIO1{slash}RXD1-Pad3)") (class "Default")
      (node (ref "GPS1") (pin "3") (pinfunction "GPIO1/RXD1_3") (pintype "bidirectional"))
    )
    (net (code "58") (name "unconnected-(GPS1-GPIO2{slash}TXD1-Pad8)") (class "Default")
      (node (ref "GPS1") (pin "8") (pinfunction "GPIO2/TXD1_8") (pintype "bidirectional"))
    )
    (net (code "59") (name "unconnected-(GPS1-GPIO3{slash}P1PPS1-Pad40)") (class "Default")
      (node (ref "GPS1") (pin "40") (pinfunction "GPIO3/P1PPS1_40") (pintype "bidirectional"))
    )
    (net (code "60") (name "unconnected-(GPS1-GPIO4{slash}SCL-Pad37)") (class "Default")
      (node (ref "GPS1") (pin "37") (pinfunction "GPIO4/SCL_37") (pintype "bidirectional"))
    )
    (net (code "61") (name "unconnected-(GPS1-GPIO5{slash}SDA-Pad14)") (class "Default")
      (node (ref "GPS1") (pin "14") (pinfunction "GPIO5/SDA_14") (pintype "bidirectional"))
    )
    (net (code "62") (name "unconnected-(GPS1-GPIO6{slash}M_CSN2-Pad13)") (class "Default")
      (node (ref "GPS1") (pin "13") (pinfunction "GPIO6/M_CSN2_13") (pintype "bidirectional"))
    )
    (net (code "63") (name "unconnected-(GPS1-GPIO7{slash}P1PPS2-Pad12)") (class "Default")
      (node (ref "GPS1") (pin "12") (pinfunction "GPIO7/P1PPS2_12") (pintype "bidirectional"))
    )
    (net (code "64") (name "unconnected-(GPS1-GPIO8-Pad51)") (class "Default")
      (node (ref "GPS1") (pin "51") (pinfunction "GPIO8_51") (pintype "bidirectional"))
    )
    (net (code "65") (name "unconnected-(GPS1-GPIO9-Pad47)") (class "Default")
      (node (ref "GPS1") (pin "47") (pinfunction "GPIO9_47") (pintype "bidirectional"))
    )
    (net (code "66") (name "unconnected-(GPS1-GPIO10-Pad59)") (class "Default")
      (node (ref "GPS1") (pin "59") (pinfunction "GPIO10_59") (pintype "bidirectional"))
    )
    (net (code "67") (name "unconnected-(GPS1-GPIO11-Pad63)") (class "Default")
      (node (ref "GPS1") (pin "63") (pinfunction "GPIO11_63") (pintype "bidirectional"))
    )
    (net (code "68") (name "unconnected-(GPS1-GPIO12-Pad55)") (class "Default")
      (node (ref "GPS1") (pin "55") (pinfunction "GPIO12_55") (pintype "bidirectional"))
    )
    (net (code "69") (name "unconnected-(GPS1-GPIO13-Pad50)") (class "Default")
      (node (ref "GPS1") (pin "50") (pinfunction "GPIO13_50") (pintype "bidirectional"))
    )
    (net (code "70") (name "unconnected-(GPS1-GPIO14-Pad45)") (class "Default")
      (node (ref "GPS1") (pin "45") (pinfunction "GPIO14_45") (pintype "bidirectional"))
    )
    (net (code "71") (name "unconnected-(GPS1-GPIO15-Pad53)") (class "Default")
      (node (ref "GPS1") (pin "53") (pinfunction "GPIO15_53") (pintype "bidirectional"))
    )
    (net (code "72") (name "unconnected-(GPS1-GPIO16-Pad48)") (class "Default")
      (node (ref "GPS1") (pin "48") (pinfunction "GPIO16_48") (pintype "bidirectional"))
    )
    (net (code "73") (name "unconnected-(GPS1-GPIO20-Pad54)") (class "Default")
      (node (ref "GPS1") (pin "54") (pinfunction "GPIO20_54") (pintype "bidirectional"))
    )
    (net (code "74") (name "unconnected-(GPS1-GPIO21-Pad57)") (class "Default")
      (node (ref "GPS1") (pin "57") (pinfunction "GPIO21_57") (pintype "bidirectional"))
    )
    (net (code "75") (name "unconnected-(GPS1-GPIO22-Pad46)") (class "Default")
      (node (ref "GPS1") (pin "46") (pinfunction "GPIO22_46") (pintype "bidirectional"))
    )
    (net (code "76") (name "unconnected-(GPS1-GPIO23{slash}M_CSN0-Pad16)") (class "Default")
      (node (ref "GPS1") (pin "16") (pinfunction "GPIO23/M_CSN0_16") (pintype "bidirectional"))
    )
    (net (code "77") (name "unconnected-(GPS1-GPIO24{slash}M_SCK-Pad5)") (class "Default")
      (node (ref "GPS1") (pin "5") (pinfunction "GPIO24/M_SCK_5") (pintype "bidirectional"))
    )
    (net (code "78") (name "unconnected-(GPS1-GPIO25{slash}M_MISO-Pad4)") (class "Default")
      (node (ref "GPS1") (pin "4") (pinfunction "GPIO25/M_MISO_4") (pintype "bidirectional"))
    )
    (net (code "79") (name "unconnected-(GPS1-GPIO26{slash}M_MOSI-Pad6)") (class "Default")
      (node (ref "GPS1") (pin "6") (pinfunction "GPIO26/M_MOSI_6") (pintype "bidirectional"))
    )
    (net (code "80") (name "unconnected-(GPS1-GPIO27-Pad52)") (class "Default")
      (node (ref "GPS1") (pin "52") (pinfunction "GPIO27_52") (pintype "bidirectional"))
    )
    (net (code "81") (name "unconnected-(GPS1-GPIO28{slash}MS_CSN-Pad43)") (class "Default")
      (node (ref "GPS1") (pin "43") (pinfunction "GPIO28/MS_CSN_43") (pintype "bidirectional"))
    )
    (net (code "82") (name "unconnected-(GPS1-GPIO29{slash}MS_SCK-Pad41)") (class "Default")
      (node (ref "GPS1") (pin "41") (pinfunction "GPIO29/MS_SCK_41") (pintype "bidirectional"))
    )
    (net (code "83") (name "unconnected-(GPS1-GPIO30{slash}MS_MOSI-Pad38)") (class "Default")
      (node (ref "GPS1") (pin "38") (pinfunction "GPIO30/MS_MOSI_38") (pintype "bidirectional"))
    )
    (net (code "84") (name "unconnected-(GPS1-GPIO31{slash}MS_MISO-Pad39)") (class "Default")
      (node (ref "GPS1") (pin "39") (pinfunction "GPIO31/MS_MISO_39") (pintype "bidirectional"))
    )
    (net (code "85") (name "unconnected-(GPS1-NC-Pad17)") (class "Default")
      (node (ref "GPS1") (pin "17") (pinfunction "NC_17") (pintype "bidirectional"))
    )
    (net (code "86") (name "unconnected-(GPS1-NC-Pad20)") (class "Default")
      (node (ref "GPS1") (pin "20") (pinfunction "NC_20") (pintype "bidirectional"))
    )
    (net (code "87") (name "unconnected-(GPS1-NC-Pad23)") (class "Default")
      (node (ref "GPS1") (pin "23") (pinfunction "NC_23") (pintype "bidirectional"))
    )
    (net (code "88") (name "unconnected-(GPS1-NC-Pad26)") (class "Default")
      (node (ref "GPS1") (pin "26") (pinfunction "NC_26") (pintype "bidirectional"))
    )
    (net (code "89") (name "unconnected-(GPS1-NC-Pad30)") (class "Default")
      (node (ref "GPS1") (pin "30") (pinfunction "NC_30") (pintype "bidirectional"))
    )
    (net (code "90") (name "unconnected-(GPS1-NC-Pad34)") (class "Default")
      (node (ref "GPS1") (pin "34") (pinfunction "NC_34") (pintype "bidirectional"))
    )
    (net (code "91") (name "unconnected-(GPS1-NC-Pad35)") (class "Default")
      (node (ref "GPS1") (pin "35") (pinfunction "NC_35") (pintype "bidirectional"))
    )
    (net (code "92") (name "unconnected-(GPS1-NC-Pad36)") (class "Default")
      (node (ref "GPS1") (pin "36") (pinfunction "NC_36") (pintype "bidirectional"))
    )
    (net (code "93") (name "unconnected-(GPS1-NC-Pad56)") (class "Default")
      (node (ref "GPS1") (pin "56") (pinfunction "NC_56") (pintype "bidirectional"))
    )
    (net (code "94") (name "unconnected-(GPS1-NC-Pad66)") (class "Default")
      (node (ref "GPS1") (pin "66") (pinfunction "NC_66") (pintype "bidirectional"))
    )
    (net (code "95") (name "unconnected-(GPS1-NC-Pad67)") (class "Default")
      (node (ref "GPS1") (pin "67") (pinfunction "NC_67") (pintype "bidirectional"))
    )
    (net (code "96") (name "unconnected-(GPS1-NC-Pad68)") (class "Default")
      (node (ref "GPS1") (pin "68") (pinfunction "NC_68") (pintype "bidirectional"))
    )
    (net (code "97") (name "unconnected-(IMU1-DEN_A{slash}G-Pad13)") (class "Default")
      (node (ref "IMU1") (pin "13") (pinfunction "DEN_A/G_13") (pintype "bidirectional"))
    )
    (net (code "98") (name "unconnected-(IMU1-INT_M-Pad10)") (class "Default")
      (node (ref "IMU1") (pin "10") (pinfunction "INT_M_10") (pintype "bidirectional"))
    )
    (net (code "99") (name "unconnected-(MICROCONTROLLER1-Pad14)") (class "Default")
      (node (ref "MICROCONTROLLER1") (pin "14") (pinfunction "14_14") (pintype "bidirectional"))
    )
    (net (code "100") (name "unconnected-(MICROCONTROLLER1-Pad15)") (class "Default")
      (node (ref "MICROCONTROLLER1") (pin "15") (pinfunction "15_15") (pintype "bidirectional"))
    )
    (net (code "101") (name "unconnected-(MICROCONTROLLER1-Pad16)") (class "Default")
      (node (ref "MICROCONTROLLER1") (pin "16") (pinfunction "16_16") (pintype "bidirectional"))
    )
    (net (code "102") (name "unconnected-(MICROCONTROLLER1-Pad17)") (class "Default")
      (node (ref "MICROCONTROLLER1") (pin "17") (pinfunction "17_17") (pintype "bidirectional"))
    )
    (net (code "103") (name "unconnected-(MICROCONTROLLER1-Pad21)") (class "Default")
      (node (ref "MICROCONTROLLER1") (pin "21") (pinfunction "21_21") (pintype "bidirectional"))
    )
    (net (code "104") (name "unconnected-(MICROCONTROLLER1-Pad29)") (class "Default")
      (node (ref "MICROCONTROLLER1") (pin "29") (pinfunction "29_29") (pintype "bidirectional"))
    )
    (net (code "105") (name "unconnected-(MICROCONTROLLER1-Pad30)") (class "Default")
      (node (ref "MICROCONTROLLER1") (pin "30") (pinfunction "30_30") (pintype "bidirectional"))
    )
    (net (code "106") (name "unconnected-(MICROCONTROLLER1-Pad31)") (class "Default")
      (node (ref "MICROCONTROLLER1") (pin "31") (pinfunction "31_31") (pintype "bidirectional"))
    )
    (net (code "107") (name "unconnected-(MICROCONTROLLER1-Pad38)") (class "Default")
      (node (ref "MICROCONTROLLER1") (pin "38") (pinfunction "38_38") (pintype "bidirectional"))
    )
    (net (code "108") (name "unconnected-(MICROCONTROLLER1-Pad39)") (class "Default")
      (node (ref "MICROCONTROLLER1") (pin "39") (pinfunction "39_39") (pintype "input"))
    )
    (net (code "109") (name "unconnected-(MICROCONTROLLER1-Pad42)") (class "Default")
      (node (ref "MICROCONTROLLER1") (pin "42") (pinfunction "42_42") (pintype "bidirectional"))
    )
    (net (code "110") (name "unconnected-(MICROCONTROLLER1-Pad43)") (class "Default")
      (node (ref "MICROCONTROLLER1") (pin "43") (pinfunction "43_43") (pintype "bidirectional"))
    )
    (net (code "111") (name "unconnected-(U$10-PadNC)") (class "Default")
      (node (ref "U$10") (pin "NC") (pinfunction "NC_NC") (pintype "bidirectional"))
    )
    (net (code "112") (name "unconnected-(U$15-LBI-Pad2)") (class "Default")
      (node (ref "U$15") (pin "2") (pinfunction "LBI_2") (pintype "bidirectional"))
    )
    (net (code "113") (name "unconnected-(U$15-LBO-Pad3)") (class "Default")
      (node (ref "U$15") (pin "3") (pinfunction "LBO_3") (pintype "bidirectional"))
    )
    (net (code "114") (name "unconnected-(U$15-REF-Pad4)") (class "Default")
      (node (ref "U$15") (pin "4") (pinfunction "REF_4") (pintype "bidirectional"))
    )
  )
)
